# RING.net
KiCad netlist of a schematic drawn in Altium Designer
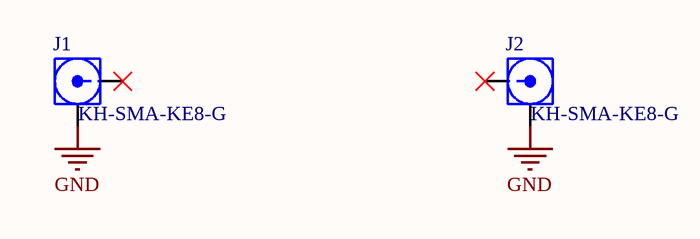
[diagram p0: RING.SchDoc]

(export (version "E")
  (design (tool "Eeschema 10.0.6"))
  (components
    (comp (ref "J1")
      (value "KH-SMA-KE8-G")
      (footprint "KH-SMA-KE8-G")
      (description "Connector RF SMA Generic")
      (fields (field (name "MANUFACTURER") "Shenzhen Kinghelm Electron Co"))
      (libsource (lib "Titan") (part "CONN_RF_SMA"))
    )
    (comp (ref "J2")
      (value "KH-SMA-KE8-G")
      (footprint "KH-SMA-KE8-G")
      (description "Connector RF SMA Generic")
      (fields (field (name "MANUFACTURER") "Shenzhen Kinghelm Electron Co"))
      (libsource (lib "Titan") (part "CONN_RF_SMA"))
    )
  )
  (nets
    (net (code "1") (name "GND") (class "Default")
      (node (ref "J1") (pin "2") (pintype "passive"))
      (node (ref "J2") (pin "2") (pintype "passive"))
    )
    (net (code "2") (name "unconnected-(J1-Pad1)") (class "Default")
      (node (ref "J1") (pin "1") (pintype "passive+no_connect"))
    )
    (net (code "3") (name "unconnected-(J2-Pad1)") (class "Default")
      (node (ref "J2") (pin "1") (pintype "passive+no_connect"))
    )
  )
)
